# TLE6244x.net
KiCad netlist of a schematic drawn in Altium Designer
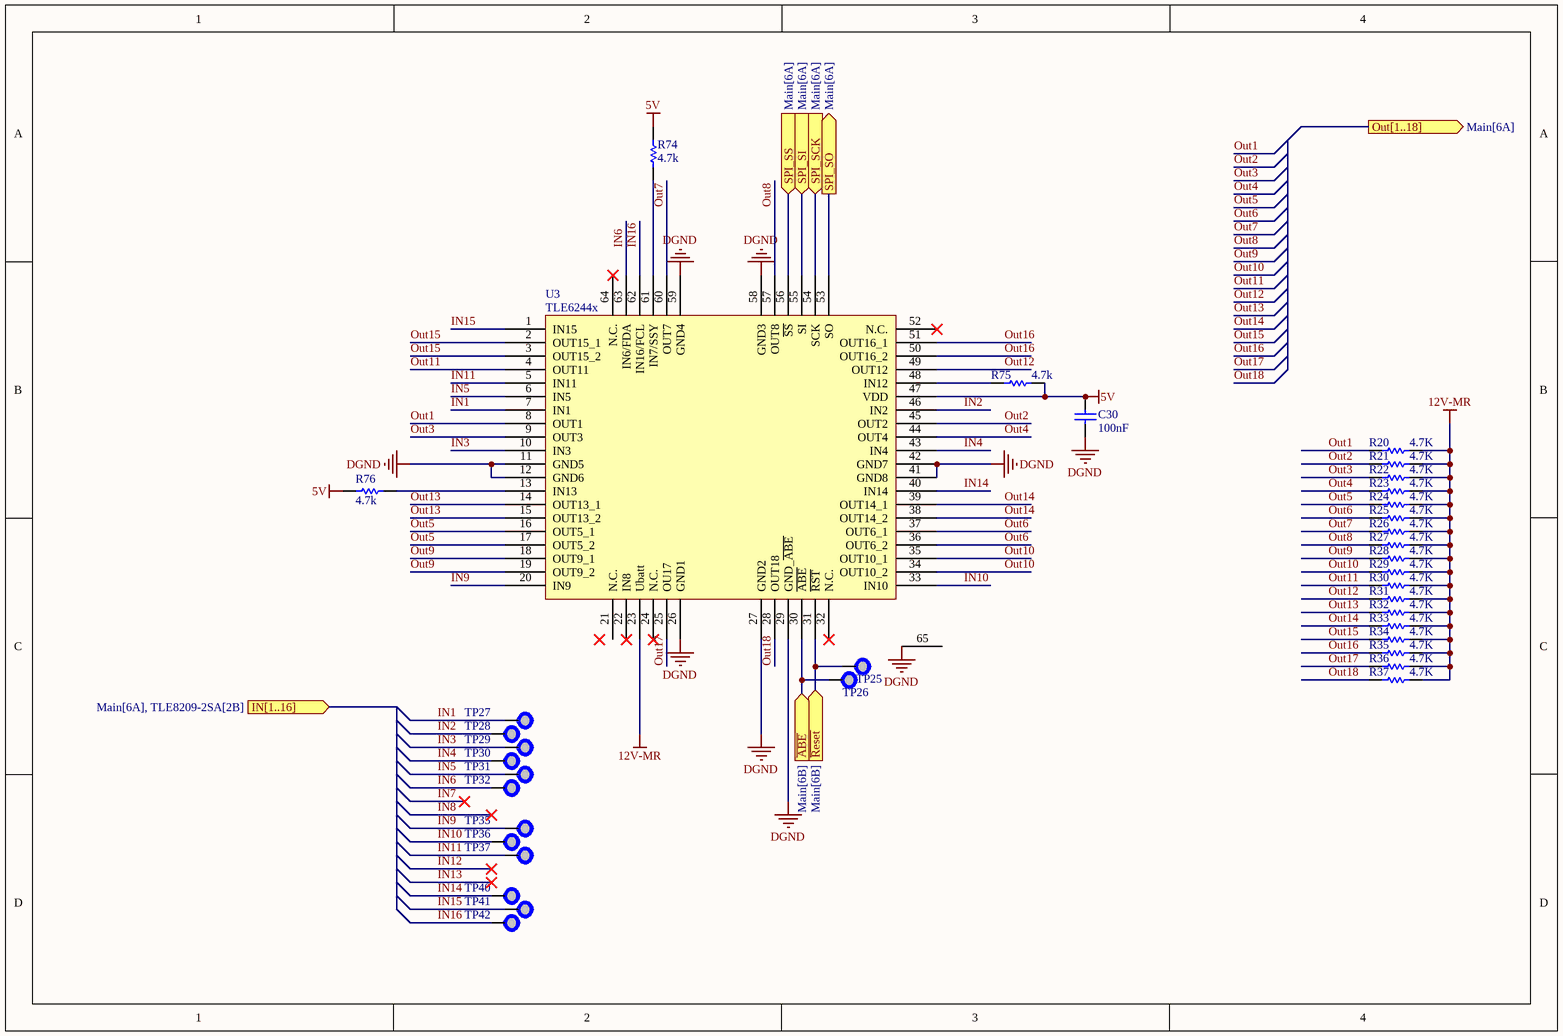
[diagram p0: TLE6244x.SchDoc]

(export (version "E")
  (design (tool "Eeschema 10.0.6"))
  (components
    (comp (ref "C30")
      (value "100nF")
      (footprint "0603c")
      (description "LOW ESR")
      (fields (field (name "PUBLISHER") "Altium Limited"))
      (libsource (lib "Miscellaneous Devices") (part "Cap"))
    )
    (comp (ref "R20")
      (value "4.7K")
      (footprint "0805")
      (description "Resistor")
      (fields (field (name "PUBLISHER") "Altium Limited"))
      (libsource (lib "Miscellaneous Devices") (part "Res1"))
    )
    (comp (ref "R21")
      (value "4.7K")
      (footprint "0805")
      (description "Resistor")
      (fields (field (name "PUBLISHER") "Altium Limited"))
      (libsource (lib "Miscellaneous Devices") (part "Res1"))
    )
    (comp (ref "R22")
      (value "4.7K")
      (footprint "0805")
      (description "Resistor")
      (fields (field (name "PUBLISHER") "Altium Limited"))
      (libsource (lib "Miscellaneous Devices") (part "Res1"))
    )
    (comp (ref "R23")
      (value "4.7K")
      (footprint "0805")
      (description "Resistor")
      (fields (field (name "PUBLISHER") "Altium Limited"))
      (libsource (lib "Miscellaneous Devices") (part "Res1"))
    )
    (comp (ref "R24")
      (value "4.7K")
      (footprint "0805")
      (description "Resistor")
      (fields (field (name "PUBLISHER") "Altium Limited"))
      (libsource (lib "Miscellaneous Devices") (part "Res1"))
    )
    (comp (ref "R25")
      (value "4.7K")
      (footprint "0805")
      (description "Resistor")
      (fields (field (name "PUBLISHER") "Altium Limited"))
      (libsource (lib "Miscellaneous Devices") (part "Res1"))
    )
    (comp (ref "R26")
      (value "4.7K")
      (footprint "0805")
      (description "Resistor")
      (fields (field (name "PUBLISHER") "Altium Limited"))
      (libsource (lib "Miscellaneous Devices") (part "Res1"))
    )
    (comp (ref "R27")
      (value "4.7K")
      (footprint "0805")
      (description "Resistor")
      (fields (field (name "PUBLISHER") "Altium Limited"))
      (libsource (lib "Miscellaneous Devices") (part "Res1"))
    )
    (comp (ref "R28")
      (value "4.7K")
      (footprint "0805")
      (description "Resistor")
      (fields (field (name "PUBLISHER") "Altium Limited"))
      (libsource (lib "Miscellaneous Devices") (part "Res1"))
    )
    (comp (ref "R29")
      (value "4.7K")
      (footprint "0805")
      (description "Resistor")
      (fields (field (name "PUBLISHER") "Altium Limited"))
      (libsource (lib "Miscellaneous Devices") (part "Res1"))
    )
    (comp (ref "R30")
      (value "4.7K")
      (footprint "0805")
      (description "Resistor")
      (fields (field (name "PUBLISHER") "Altium Limited"))
      (libsource (lib "Miscellaneous Devices") (part "Res1"))
    )
    (comp (ref "R31")
      (value "4.7K")
      (footprint "0805")
      (description "Resistor")
      (fields (field (name "PUBLISHER") "Altium Limited"))
      (libsource (lib "Miscellaneous Devices") (part "Res1"))
    )
    (comp (ref "R32")
      (value "4.7K")
      (footprint "0805")
      (description "Resistor")
      (fields (field (name "PUBLISHER") "Altium Limited"))
      (libsource (lib "Miscellaneous Devices") (part "Res1"))
    )
    (comp (ref "R33")
      (value "4.7K")
      (footprint "0805")
      (description "Resistor")
      (fields (field (name "PUBLISHER") "Altium Limited"))
      (libsource (lib "Miscellaneous Devices") (part "Res1"))
    )
    (comp (ref "R34")
      (value "4.7K")
      (footprint "0805")
      (description "Resistor")
      (fields (field (name "PUBLISHER") "Altium Limited"))
      (libsource (lib "Miscellaneous Devices") (part "Res1"))
    )
    (comp (ref "R35")
      (value "4.7K")
      (footprint "0805")
      (description "Resistor")
      (fields (field (name "PUBLISHER") "Altium Limited"))
      (libsource (lib "Miscellaneous Devices") (part "Res1"))
    )
    (comp (ref "R36")
      (value "4.7K")
      (footprint "0805")
      (description "Resistor")
      (fields (field (name "PUBLISHER") "Altium Limited"))
      (libsource (lib "Miscellaneous Devices") (part "Res1"))
    )
    (comp (ref "R37")
      (value "4.7K")
      (footprint "0805")
      (description "Resistor")
      (fields (field (name "PUBLISHER") "Altium Limited"))
      (libsource (lib "Miscellaneous Devices") (part "Res1"))
    )
    (comp (ref "R74")
      (value "4.7k")
      (footprint "0805")
      (description "Resistor")
      (fields (field (name "Comment") "4.7K") (field (name "PUBLISHER") "Altium Limited"))
      (libsource (lib "Miscellaneous Devices") (part "Res1"))
    )
    (comp (ref "R75")
      (value "4.7k")
      (footprint "0805")
      (description "Resistor")
      (fields (field (name "Comment") "4.7K") (field (name "PUBLISHER") "Altium Limited"))
      (libsource (lib "Miscellaneous Devices") (part "Res1"))
    )
    (comp (ref "R76")
      (value "4.7k")
      (footprint "0805")
      (description "Resistor")
      (fields (field (name "Comment") "4.7K") (field (name "PUBLISHER") "Altium Limited"))
      (libsource (lib "Miscellaneous Devices") (part "Res1"))
    )
    (comp (ref "TP25") (value "TestPoint") (footprint "TP") (libsource (lib "SchlibV0.1") (part "TestPoint")))
    (comp (ref "TP26") (value "TestPoint") (footprint "TP") (libsource (lib "SchlibV0.1") (part "TestPoint")))
    (comp (ref "TP27") (value "TestPoint") (footprint "TP") (libsource (lib "SchlibV0.1") (part "TestPoint")))
    (comp (ref "TP28") (value "TestPoint") (footprint "TP") (libsource (lib "SchlibV0.1") (part "TestPoint")))
    (comp (ref "TP29") (value "TestPoint") (footprint "TP") (libsource (lib "SchlibV0.1") (part "TestPoint")))
    (comp (ref "TP30") (value "TestPoint") (footprint "TP") (libsource (lib "SchlibV0.1") (part "TestPoint")))
    (comp (ref "TP31") (value "TestPoint") (footprint "TP") (libsource (lib "SchlibV0.1") (part "TestPoint")))
    (comp (ref "TP32") (value "TestPoint") (footprint "TP") (libsource (lib "SchlibV0.1") (part "TestPoint")))
    (comp (ref "TP35") (value "TestPoint") (footprint "TP") (libsource (lib "SchlibV0.1") (part "TestPoint")))
    (comp (ref "TP36") (value "TestPoint") (footprint "TP") (libsource (lib "SchlibV0.1") (part "TestPoint")))
    (comp (ref "TP37") (value "TestPoint") (footprint "TP") (libsource (lib "SchlibV0.1") (part "TestPoint")))
    (comp (ref "TP40") (value "TestPoint") (footprint "TP") (libsource (lib "SchlibV0.1") (part "TestPoint")))
    (comp (ref "TP41") (value "TestPoint") (footprint "TP") (libsource (lib "SchlibV0.1") (part "TestPoint")))
    (comp (ref "TP42") (value "TestPoint") (footprint "TP") (libsource (lib "SchlibV0.1") (part "TestPoint")))
    (comp (ref "U3")
      (value "TLE6244x")
      (footprint "TLE6244")
      (description "PG-MQFP-64-10")
      (fields (field (name "MANUFACTURER") "Infineon") (field (name "PART NUMBER") "TLE6244X"))
      (libsource (lib "TLE 6244X") (part "TLE6244x"))
    )
  )
  (nets
    (net (code "1") (name "/IN1") (class "Default")
      (node (ref "TP27") (pin "1") (pintype "passive"))
      (node (ref "U3") (pin "7") (pinfunction "IN1_7") (pintype "passive"))
    )
    (net (code "2") (name "/IN2") (class "Default")
      (node (ref "TP28") (pin "1") (pintype "passive"))
      (node (ref "U3") (pin "46") (pinfunction "IN2_46") (pintype "passive"))
    )
    (net (code "3") (name "/IN3") (class "Default")
      (node (ref "TP29") (pin "1") (pintype "passive"))
      (node (ref "U3") (pin "10") (pinfunction "IN3_10") (pintype "passive"))
    )
    (net (code "4") (name "/IN4") (class "Default")
      (node (ref "TP30") (pin "1") (pintype "passive"))
      (node (ref "U3") (pin "43") (pinfunction "IN4_43") (pintype "passive"))
    )
    (net (code "5") (name "/IN5") (class "Default")
      (node (ref "TP31") (pin "1") (pintype "passive"))
      (node (ref "U3") (pin "6") (pinfunction "IN5_6") (pintype "passive"))
    )
    (net (code "6") (name "/IN6") (class "Default")
      (node (ref "TP32") (pin "1") (pintype "passive"))
      (node (ref "U3") (pin "63") (pinfunction "IN6/FDA_63") (pintype "passive"))
    )
    (net (code "9") (name "/IN9") (class "Default")
      (node (ref "TP35") (pin "1") (pintype "passive"))
      (node (ref "U3") (pin "20") (pinfunction "IN9_20") (pintype "passive"))
    )
    (net (code "10") (name "/IN10") (class "Default")
      (node (ref "TP36") (pin "1") (pintype "passive"))
      (node (ref "U3") (pin "33") (pinfunction "IN10_33") (pintype "passive"))
    )
    (net (code "11") (name "/IN11") (class "Default")
      (node (ref "TP37") (pin "1") (pintype "passive"))
      (node (ref "U3") (pin "5") (pinfunction "IN11_5") (pintype "passive"))
    )
    (net (code "14") (name "/IN14") (class "Default")
      (node (ref "TP40") (pin "1") (pintype "passive"))
      (node (ref "U3") (pin "40") (pinfunction "IN14_40") (pintype "passive"))
    )
    (net (code "15") (name "/IN15") (class "Default")
      (node (ref "TP41") (pin "1") (pintype "passive"))
      (node (ref "U3") (pin "1") (pinfunction "IN15_1") (pintype "passive"))
    )
    (net (code "16") (name "/IN16") (class "Default")
      (node (ref "TP42") (pin "1") (pintype "passive"))
      (node (ref "U3") (pin "62") (pinfunction "IN16/FCL_62") (pintype "passive"))
    )
    (net (code "18") (name "/Out1") (class "Default")
      (node (ref "R20") (pin "2") (pinfunction "2_2") (pintype "passive"))
      (node (ref "U3") (pin "8") (pinfunction "OUT1_8") (pintype "passive"))
    )
    (net (code "19") (name "/Out2") (class "Default")
      (node (ref "R21") (pin "2") (pinfunction "2_2") (pintype "passive"))
      (node (ref "U3") (pin "45") (pinfunction "OUT2_45") (pintype "passive"))
    )
    (net (code "20") (name "/Out3") (class "Default")
      (node (ref "R22") (pin "2") (pinfunction "2_2") (pintype "passive"))
      (node (ref "U3") (pin "9") (pinfunction "OUT3_9") (pintype "passive"))
    )
    (net (code "21") (name "/Out4") (class "Default")
      (node (ref "R23") (pin "2") (pinfunction "2_2") (pintype "passive"))
      (node (ref "U3") (pin "44") (pinfunction "OUT4_44") (pintype "passive"))
    )
    (net (code "22") (name "/Out5") (class "Default")
      (node (ref "R24") (pin "2") (pinfunction "2_2") (pintype "passive"))
      (node (ref "U3") (pin "16") (pinfunction "OUT5_1_16") (pintype "passive"))
      (node (ref "U3") (pin "17") (pinfunction "OUT5_2_17") (pintype "passive"))
    )
    (net (code "23") (name "/Out6") (class "Default")
      (node (ref "R25") (pin "2") (pinfunction "2_2") (pintype "passive"))
      (node (ref "U3") (pin "36") (pinfunction "OUT6_2_36") (pintype "passive"))
      (node (ref "U3") (pin "37") (pinfunction "OUT6_1_37") (pintype "passive"))
    )
    (net (code "24") (name "/Out7") (class "Default")
      (node (ref "R26") (pin "2") (pinfunction "2_2") (pintype "passive"))
      (node (ref "U3") (pin "60") (pinfunction "OUT7_60") (pintype "passive"))
    )
    (net (code "25") (name "/Out8") (class "Default")
      (node (ref "R27") (pin "2") (pinfunction "2_2") (pintype "passive"))
      (node (ref "U3") (pin "57") (pinfunction "OUT8_57") (pintype "passive"))
    )
    (net (code "26") (name "/Out9") (class "Default")
      (node (ref "R28") (pin "2") (pinfunction "2_2") (pintype "passive"))
      (node (ref "U3") (pin "18") (pinfunction "OUT9_1_18") (pintype "passive"))
      (node (ref "U3") (pin "19") (pinfunction "OUT9_2_19") (pintype "passive"))
    )
    (net (code "27") (name "/Out10") (class "Default")
      (node (ref "R29") (pin "2") (pinfunction "2_2") (pintype "passive"))
      (node (ref "U3") (pin "34") (pinfunction "OUT10_2_34") (pintype "passive"))
      (node (ref "U3") (pin "35") (pinfunction "OUT10_1_35") (pintype "passive"))
    )
    (net (code "28") (name "/Out11") (class "Default")
      (node (ref "R30") (pin "2") (pinfunction "2_2") (pintype "passive"))
      (node (ref "U3") (pin "4") (pinfunction "OUT11_4") (pintype "passive"))
    )
    (net (code "29") (name "/Out12") (class "Default")
      (node (ref "R31") (pin "2") (pinfunction "2_2") (pintype "passive"))
      (node (ref "U3") (pin "49") (pinfunction "OUT12_49") (pintype "passive"))
    )
    (net (code "30") (name "/Out13") (class "Default")
      (node (ref "R32") (pin "2") (pinfunction "2_2") (pintype "passive"))
      (node (ref "U3") (pin "14") (pinfunction "OUT13_1_14") (pintype "passive"))
      (node (ref "U3") (pin "15") (pinfunction "OUT13_2_15") (pintype "passive"))
    )
    (net (code "31") (name "/Out14") (class "Default")
      (node (ref "R33") (pin "2") (pinfunction "2_2") (pintype "passive"))
      (node (ref "U3") (pin "38") (pinfunction "OUT14_2_38") (pintype "passive"))
      (node (ref "U3") (pin "39") (pinfunction "OUT14_1_39") (pintype "passive"))
    )
    (net (code "32") (name "/Out15") (class "Default")
      (node (ref "R34") (pin "2") (pinfunction "2_2") (pintype "passive"))
      (node (ref "U3") (pin "2") (pinfunction "OUT15_1_2") (pintype "passive"))
      (node (ref "U3") (pin "3") (pinfunction "OUT15_2_3") (pintype "passive"))
    )
    (net (code "33") (name "/Out16") (class "Default")
      (node (ref "R35") (pin "2") (pinfunction "2_2") (pintype "passive"))
      (node (ref "U3") (pin "50") (pinfunction "OUT16_2_50") (pintype "passive"))
      (node (ref "U3") (pin "51") (pinfunction "OUT16_1_51") (pintype "passive"))
    )
    (net (code "34") (name "/Out17") (class "Default")
      (node (ref "R36") (pin "2") (pinfunction "2_2") (pintype "passive"))
      (node (ref "U3") (pin "25") (pinfunction "OU17_25") (pintype "passive"))
    )
    (net (code "35") (name "/Out18") (class "Default")
      (node (ref "R37") (pin "2") (pinfunction "2_2") (pintype "passive"))
      (node (ref "U3") (pin "28") (pinfunction "OUT18_28") (pintype "passive"))
    )
    (net (code "37") (name "/SPI_SCK") (class "Default")
      (node (ref "U3") (pin "54") (pinfunction "SCK_54") (pintype "passive"))
    )
    (net (code "38") (name "/SPI_SI") (class "Default")
      (node (ref "U3") (pin "55") (pinfunction "SI_55") (pintype "passive"))
    )
    (net (code "39") (name "/SPI_SO") (class "Default")
      (node (ref "U3") (pin "53") (pinfunction "SO_53") (pintype "passive"))
    )
    (net (code "40") (name "/SPI_SS") (class "Default")
      (node (ref "U3") (pin "56") (pinfunction "~{SS}_56") (pintype "passive"))
    )
    (net (code "41") (name "/~{ABE}") (class "Default")
      (node (ref "TP26") (pin "1") (pintype "passive"))
      (node (ref "U3") (pin "30") (pinfunction "~{ABE}_30") (pintype "passive"))
    )
    (net (code "42") (name "/~{Reset}") (class "Default")
      (node (ref "TP25") (pin "1") (pintype "passive"))
      (node (ref "U3") (pin "31") (pinfunction "~{RST}_31") (pintype "passive"))
    )
    (net (code "43") (name "5V") (class "Default")
      (node (ref "C30") (pin "1") (pinfunction "1_1") (pintype "passive"))
      (node (ref "R74") (pin "2") (pinfunction "2_2") (pintype "passive"))
      (node (ref "R75") (pin "1") (pinfunction "1_1") (pintype "passive"))
      (node (ref "R76") (pin "2") (pinfunction "2_2") (pintype "passive"))
      (node (ref "U3") (pin "47") (pinfunction "VDD_47") (pintype "passive"))
    )
    (net (code "44") (name "12V-MR") (class "Default")
      (node (ref "R20") (pin "1") (pinfunction "1_1") (pintype "passive"))
      (node (ref "R21") (pin "1") (pinfunction "1_1") (pintype "passive"))
      (node (ref "R22") (pin "1") (pinfunction "1_1") (pintype "passive"))
      (node (ref "R23") (pin "1") (pinfunction "1_1") (pintype "passive"))
      (node (ref "R24") (pin "1") (pinfunction "1_1") (pintype "passive"))
      (node (ref "R25") (pin "1") (pinfunction "1_1") (pintype "passive"))
      (node (ref "R26") (pin "1") (pinfunction "1_1") (pintype "passive"))
      (node (ref "R27") (pin "1") (pinfunction "1_1") (pintype "passive"))
      (node (ref "R28") (pin "1") (pinfunction "1_1") (pintype "passive"))
      (node (ref "R29") (pin "1") (pinfunction "1_1") (pintype "passive"))
      (node (ref "R30") (pin "1") (pinfunction "1_1") (pintype "passive"))
      (node (ref "R31") (pin "1") (pinfunction "1_1") (pintype "passive"))
      (node (ref "R32") (pin "1") (pinfunction "1_1") (pintype "passive"))
      (node (ref "R33") (pin "1") (pinfunction "1_1") (pintype "passive"))
      (node (ref "R34") (pin "1") (pinfunction "1_1") (pintype "passive"))
      (node (ref "R35") (pin "1") (pinfunction "1_1") (pintype "passive"))
      (node (ref "R36") (pin "1") (pinfunction "1_1") (pintype "passive"))
      (node (ref "R37") (pin "1") (pinfunction "1_1") (pintype "passive"))
      (node (ref "U3") (pin "23") (pinfunction "Ubatt_23") (pintype "passive"))
    )
    (net (code "45") (name "DGND") (class "Default")
      (node (ref "C30") (pin "2") (pinfunction "2_2") (pintype "passive"))
      (node (ref "U3") (pin "11") (pinfunction "GND5_11") (pintype "passive"))
      (node (ref "U3") (pin "12") (pinfunction "GND6_12") (pintype "passive"))
      (node (ref "U3") (pin "26") (pinfunction "GND1_26") (pintype "passive"))
      (node (ref "U3") (pin "27") (pinfunction "GND2_27") (pintype "passive"))
      (node (ref "U3") (pin "29") (pinfunction "GND_~{ABE}_29") (pintype "passive"))
      (node (ref "U3") (pin "41") (pinfunction "GND8_41") (pintype "passive"))
      (node (ref "U3") (pin "42") (pinfunction "GND7_42") (pintype "passive"))
      (node (ref "U3") (pin "58") (pinfunction "GND3_58") (pintype "passive"))
      (node (ref "U3") (pin "59") (pinfunction "GND4_59") (pintype "passive"))
      (node (ref "U3") (pin "65") (pinfunction "DGND_65") (pintype "passive"))
    )
    (net (code "46") (name "Net-(U3-IN7{slash}SSY)") (class "Default")
      (node (ref "R74") (pin "1") (pinfunction "1_1") (pintype "passive"))
      (node (ref "U3") (pin "61") (pinfunction "IN7/SSY_61") (pintype "passive"))
    )
    (net (code "47") (name "Net-(U3-IN12)") (class "Default")
      (node (ref "R75") (pin "2") (pinfunction "2_2") (pintype "passive"))
      (node (ref "U3") (pin "48") (pinfunction "IN12_48") (pintype "passive"))
    )
    (net (code "48") (name "Net-(U3-IN13)") (class "Default")
      (node (ref "R76") (pin "1") (pinfunction "1_1") (pintype "passive"))
      (node (ref "U3") (pin "13") (pinfunction "IN13_13") (pintype "passive"))
    )
    (net (code "49") (name "unconnected-(U3-IN8-Pad22)") (class "Default")
      (node (ref "U3") (pin "22") (pinfunction "IN8_22") (pintype "passive+no_connect"))
    )
    (net (code "50") (name "unconnected-(U3-N.C.-Pad21)") (class "Default")
      (node (ref "U3") (pin "21") (pinfunction "N.C._21") (pintype "passive"))
    )
    (net (code "51") (name "unconnected-(U3-N.C.-Pad24)") (class "Default")
      (node (ref "U3") (pin "24") (pinfunction "N.C._24") (pintype "passive+no_connect"))
    )
    (net (code "52") (name "unconnected-(U3-N.C.-Pad32)") (class "Default")
      (node (ref "U3") (pin "32") (pinfunction "N.C._32") (pintype "passive+no_connect"))
    )
    (net (code "53") (name "unconnected-(U3-N.C.-Pad52)") (class "Default")
      (node (ref "U3") (pin "52") (pinfunction "N.C._52") (pintype "passive+no_connect"))
    )
    (net (code "54") (name "unconnected-(U3-N.C.-Pad64)") (class "Default")
      (node (ref "U3") (pin "64") (pinfunction "N.C._64") (pintype "passive+no_connect"))
    )
  )
)
